# CAT-control-V1.net
KiCad netlist of a schematic drawn in EAGLE
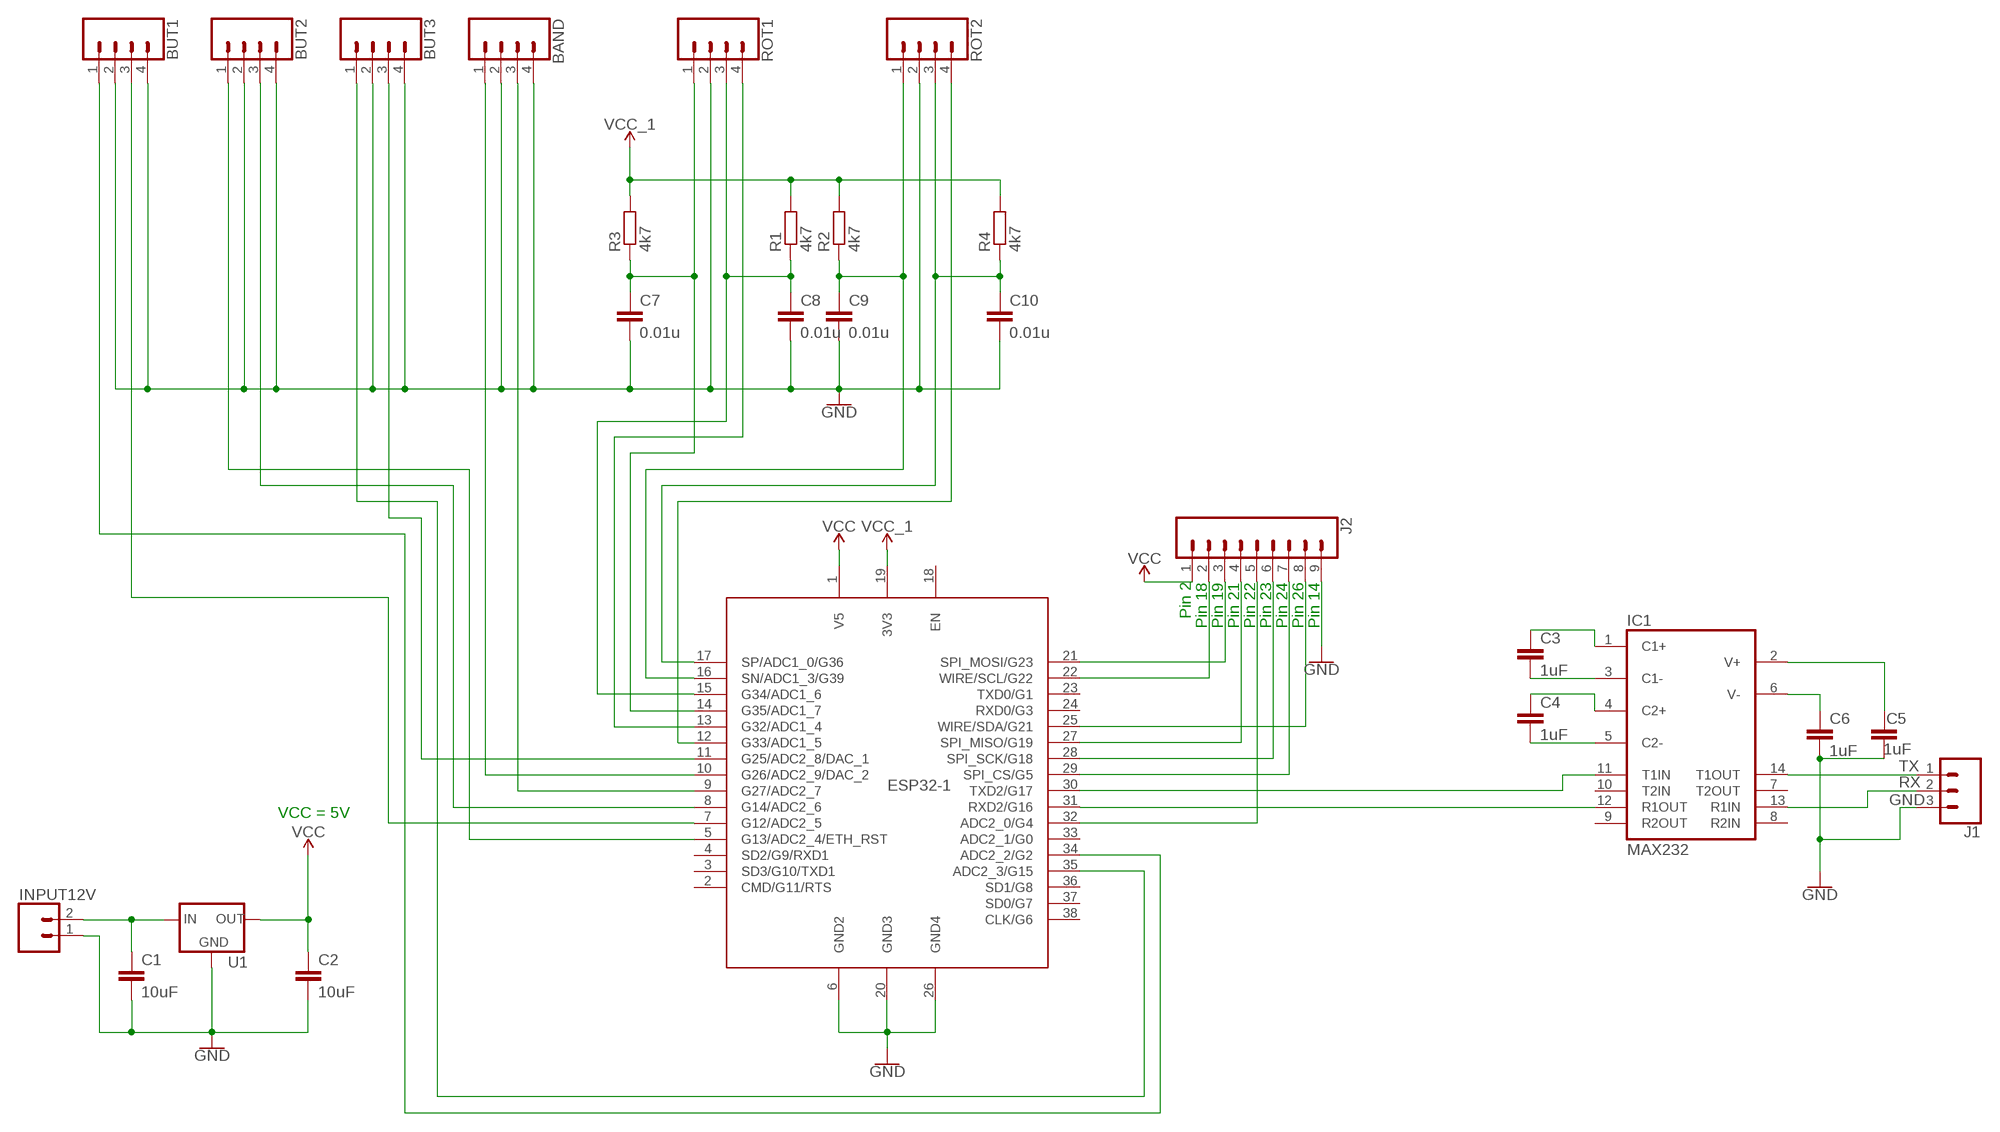
[diagram p0: schematic, sheet 1]

(export (version "E")
  (design (tool "Eeschema 10.0.6"))
  (components
    (comp (ref "BAND")
      (value "CONN_04POLAR")
      (footprint "eagle-import:MOLEX-1X4")
      (libsource (lib "eagle-import") (part "CONN_04POLAR"))
    )
    (comp (ref "BUT1")
      (value "CONN_04POLAR")
      (footprint "eagle-import:MOLEX-1X4")
      (libsource (lib "eagle-import") (part "CONN_04POLAR"))
    )
    (comp (ref "BUT2")
      (value "CONN_04POLAR")
      (footprint "eagle-import:MOLEX-1X4")
      (libsource (lib "eagle-import") (part "CONN_04POLAR"))
    )
    (comp (ref "BUT3")
      (value "CONN_04POLAR")
      (footprint "eagle-import:MOLEX-1X4")
      (libsource (lib "eagle-import") (part "CONN_04POLAR"))
    )
    (comp (ref "C1")
      (value "10uF")
      (footprint "eagle-import:C1206")
      (libsource (lib "eagle-import") (part "CAPACITORS-EUC1206"))
    )
    (comp (ref "C2")
      (value "10uF")
      (footprint "eagle-import:C1206")
      (libsource (lib "eagle-import") (part "CAPACITORS-EUC1206"))
    )
    (comp (ref "C3")
      (value "1uF")
      (footprint "eagle-import:C1206")
      (libsource (lib "eagle-import") (part "CAPACITORS-EUC1206"))
    )
    (comp (ref "C4")
      (value "1uF")
      (footprint "eagle-import:C1206")
      (libsource (lib "eagle-import") (part "CAPACITORS-EUC1206"))
    )
    (comp (ref "C5")
      (value "1uF")
      (footprint "eagle-import:C1206")
      (libsource (lib "eagle-import") (part "CAPACITORS-EUC1206"))
    )
    (comp (ref "C6")
      (value "1uF")
      (footprint "eagle-import:C1206")
      (libsource (lib "eagle-import") (part "CAPACITORS-EUC1206"))
    )
    (comp (ref "C7")
      (value "0.01u")
      (footprint "eagle-import:C025-024X044")
      (libsource (lib "eagle-import") (part "CAPACITORS-EU025-024X044"))
    )
    (comp (ref "C8")
      (value "0.01u")
      (footprint "eagle-import:C025-024X044")
      (libsource (lib "eagle-import") (part "CAPACITORS-EU025-024X044"))
    )
    (comp (ref "C9")
      (value "0.01u")
      (footprint "eagle-import:C025-024X044")
      (libsource (lib "eagle-import") (part "CAPACITORS-EU025-024X044"))
    )
    (comp (ref "C10")
      (value "0.01u")
      (footprint "eagle-import:C025-024X044")
      (libsource (lib "eagle-import") (part "CAPACITORS-EU025-024X044"))
    )
    (comp (ref "ESP32-1")
      (value "NODEMCU_ESP32_WROOM_32")
      (footprint "eagle-import:NODEMCU_ESP32_WROOM_32--38PINS")
      (libsource (lib "eagle-import") (part "NODEMCU_ESP32_WROOM_32"))
    )
    (comp (ref "IC1")
      (value "MAX232")
      (footprint "eagle-import:DIL16")
      (fields (field (name "MF") "MAXIM") (field (name "MPN") "MAX232ACPE+"))
      (libsource (lib "eagle-import") (part "MAX232"))
    )
    (comp (ref "INPUT12V")
      (value "CONN_025MM")
      (footprint "eagle-import:SCREWTERMINAL-5MM-2")
      (libsource (lib "eagle-import") (part "CONN_025MM"))
    )
    (comp (ref "J1")
      (value "CONN_03SCREW")
      (footprint "eagle-import:SCREWTERMINAL-3.5MM-3")
      (libsource (lib "eagle-import") (part "CONN_03SCREW"))
    )
    (comp (ref "J2")
      (value "CONN_09")
      (footprint "eagle-import:1X09")
      (libsource (lib "eagle-import") (part "CONN_09"))
    )
    (comp (ref "R1")
      (value "4k7")
      (footprint "eagle-import:R1206")
      (libsource (lib "eagle-import") (part "RESISTORS-EUR1206"))
    )
    (comp (ref "R2")
      (value "4k7")
      (footprint "eagle-import:R1206")
      (libsource (lib "eagle-import") (part "RESISTORS-EUR1206"))
    )
    (comp (ref "R3")
      (value "4k7")
      (footprint "eagle-import:R1206")
      (libsource (lib "eagle-import") (part "RESISTORS-EUR1206"))
    )
    (comp (ref "R4")
      (value "4k7")
      (footprint "eagle-import:R1206")
      (libsource (lib "eagle-import") (part "RESISTORS-EUR1206"))
    )
    (comp (ref "ROT1")
      (value "CONN_04POLAR")
      (footprint "eagle-import:MOLEX-1X4")
      (libsource (lib "eagle-import") (part "CONN_04POLAR"))
    )
    (comp (ref "ROT2")
      (value "CONN_04POLAR")
      (footprint "eagle-import:MOLEX-1X4")
      (libsource (lib "eagle-import") (part "CONN_04POLAR"))
    )
    (comp (ref "U1")
      (value "V_REG_78XXSINK")
      (footprint "eagle-import:TO220-IGO")
      (libsource (lib "eagle-import") (part "V_REG_78XXSINK"))
    )
  )
  (nets
    (net (code "1") (name "/CMD{slash}G11{slash}RTS") (class "Default")
      (node (ref "ESP32-1") (pin "2") (pinfunction "CMD/G11/RTS_2") (pintype "power_in"))
    )
    (net (code "2") (name "/RX") (class "Default")
      (node (ref "IC1") (pin "13") (pinfunction "R1IN_13") (pintype "input"))
      (node (ref "J1") (pin "2") (pinfunction "2_2") (pintype "passive"))
    )
    (net (code "3") (name "/TX") (class "Default")
      (node (ref "IC1") (pin "14") (pinfunction "T1OUT_14") (pintype "output"))
      (node (ref "J1") (pin "1") (pinfunction "1_1") (pintype "passive"))
    )
    (net (code "4") (name "GND") (class "Default")
      (node (ref "BAND") (pin "2") (pinfunction "2_2") (pintype "passive"))
      (node (ref "BAND") (pin "4") (pinfunction "4_4") (pintype "passive"))
      (node (ref "BUT1") (pin "2") (pinfunction "2_2") (pintype "passive"))
      (node (ref "BUT1") (pin "4") (pinfunction "4_4") (pintype "passive"))
      (node (ref "BUT2") (pin "2") (pinfunction "2_2") (pintype "passive"))
      (node (ref "BUT2") (pin "4") (pinfunction "4_4") (pintype "passive"))
      (node (ref "BUT3") (pin "2") (pinfunction "2_2") (pintype "passive"))
      (node (ref "BUT3") (pin "4") (pinfunction "4_4") (pintype "passive"))
      (node (ref "C1") (pin "2") (pinfunction "2_2") (pintype "passive"))
      (node (ref "C10") (pin "2") (pinfunction "2_2") (pintype "passive"))
      (node (ref "C2") (pin "2") (pinfunction "2_2") (pintype "passive"))
      (node (ref "C5") (pin "1") (pinfunction "1_1") (pintype "passive"))
      (node (ref "C6") (pin "2") (pinfunction "2_2") (pintype "passive"))
      (node (ref "C7") (pin "2") (pinfunction "2_2") (pintype "passive"))
      (node (ref "C8") (pin "2") (pinfunction "2_2") (pintype "passive"))
      (node (ref "C9") (pin "2") (pinfunction "2_2") (pintype "passive"))
      (node (ref "ESP32-1") (pin "20") (pinfunction "GND3_20") (pintype "power_in"))
      (node (ref "ESP32-1") (pin "26") (pinfunction "GND4_26") (pintype "power_in"))
      (node (ref "ESP32-1") (pin "6") (pinfunction "GND2_6") (pintype "power_in"))
      (node (ref "INPUT12V") (pin "1") (pinfunction "1_1") (pintype "passive"))
      (node (ref "J1") (pin "3") (pinfunction "3_3") (pintype "passive"))
      (node (ref "J2") (pin "9") (pinfunction "9_9") (pintype "passive"))
      (node (ref "ROT1") (pin "2") (pinfunction "2_2") (pintype "passive"))
      (node (ref "ROT2") (pin "2") (pinfunction "2_2") (pintype "passive"))
      (node (ref "U1") (pin "GND") (pinfunction "GND_GND") (pintype "input"))
    )
    (net (code "5") (name "Net-(C1-Pad1)") (class "Default")
      (node (ref "C1") (pin "1") (pinfunction "1_1") (pintype "passive"))
      (node (ref "INPUT12V") (pin "2") (pinfunction "2_2") (pintype "passive"))
      (node (ref "U1") (pin "IN") (pinfunction "IN_IN") (pintype "input"))
    )
    (net (code "6") (name "Net-(ESP32-1-ADC2_0{slash}G4)") (class "Default")
      (node (ref "ESP32-1") (pin "32") (pinfunction "ADC2_0/G4_32") (pintype "bidirectional"))
      (node (ref "J2") (pin "5") (pinfunction "5_5") (pintype "passive"))
    )
    (net (code "7") (name "Net-(ESP32-1-ADC2_2{slash}G2)") (class "Default")
      (node (ref "BUT1") (pin "1") (pinfunction "1_1") (pintype "passive"))
      (node (ref "ESP32-1") (pin "34") (pinfunction "ADC2_2/G2_34") (pintype "bidirectional"))
    )
    (net (code "8") (name "Net-(ESP32-1-ADC2_3{slash}G15)") (class "Default")
      (node (ref "BUT3") (pin "1") (pinfunction "1_1") (pintype "passive"))
      (node (ref "ESP32-1") (pin "35") (pinfunction "ADC2_3/G15_35") (pintype "bidirectional"))
    )
    (net (code "9") (name "Net-(ESP32-1-G12{slash}ADC2_5)") (class "Default")
      (node (ref "BUT1") (pin "3") (pinfunction "3_3") (pintype "passive"))
      (node (ref "ESP32-1") (pin "7") (pinfunction "G12/ADC2_5_7") (pintype "bidirectional"))
    )
    (net (code "10") (name "Net-(ESP32-1-G13{slash}ADC2_4{slash}ETH_RST)") (class "Default")
      (node (ref "BUT2") (pin "1") (pinfunction "1_1") (pintype "passive"))
      (node (ref "ESP32-1") (pin "5") (pinfunction "G13/ADC2_4/ETH_RST_5") (pintype "bidirectional"))
    )
    (net (code "11") (name "Net-(ESP32-1-G14{slash}ADC2_6)") (class "Default")
      (node (ref "BUT2") (pin "3") (pinfunction "3_3") (pintype "passive"))
      (node (ref "ESP32-1") (pin "8") (pinfunction "G14/ADC2_6_8") (pintype "bidirectional"))
    )
    (net (code "12") (name "Net-(ESP32-1-G25{slash}ADC2_8{slash}DAC_1)") (class "Default")
      (node (ref "BUT3") (pin "3") (pinfunction "3_3") (pintype "passive"))
      (node (ref "ESP32-1") (pin "11") (pinfunction "G25/ADC2_8/DAC_1_11") (pintype "bidirectional"))
    )
    (net (code "13") (name "Net-(ESP32-1-G26{slash}ADC2_9{slash}DAC_2)") (class "Default")
      (node (ref "BAND") (pin "1") (pinfunction "1_1") (pintype "passive"))
      (node (ref "ESP32-1") (pin "10") (pinfunction "G26/ADC2_9/DAC_2_10") (pintype "bidirectional"))
    )
    (net (code "14") (name "Net-(ESP32-1-G27{slash}ADC2_7)") (class "Default")
      (node (ref "BAND") (pin "3") (pinfunction "3_3") (pintype "passive"))
      (node (ref "ESP32-1") (pin "9") (pinfunction "G27/ADC2_7_9") (pintype "bidirectional"))
    )
    (net (code "15") (name "Net-(ESP32-1-G32{slash}ADC1_4)") (class "Default")
      (node (ref "ESP32-1") (pin "13") (pinfunction "G32/ADC1_4_13") (pintype "bidirectional"))
      (node (ref "ROT1") (pin "4") (pinfunction "4_4") (pintype "passive"))
    )
    (net (code "16") (name "Net-(ESP32-1-G33{slash}ADC1_5)") (class "Default")
      (node (ref "ESP32-1") (pin "12") (pinfunction "G33/ADC1_5_12") (pintype "bidirectional"))
      (node (ref "ROT2") (pin "4") (pinfunction "4_4") (pintype "passive"))
    )
    (net (code "17") (name "Net-(ESP32-1-G34{slash}ADC1_6)") (class "Default")
      (node (ref "C8") (pin "1") (pinfunction "1_1") (pintype "passive"))
      (node (ref "ESP32-1") (pin "15") (pinfunction "G34/ADC1_6_15") (pintype "bidirectional"))
      (node (ref "R1") (pin "1") (pinfunction "1_1") (pintype "passive"))
      (node (ref "ROT1") (pin "3") (pinfunction "3_3") (pintype "passive"))
    )
    (net (code "18") (name "Net-(ESP32-1-G35{slash}ADC1_7)") (class "Default")
      (node (ref "C7") (pin "1") (pinfunction "1_1") (pintype "passive"))
      (node (ref "ESP32-1") (pin "14") (pinfunction "G35/ADC1_7_14") (pintype "bidirectional"))
      (node (ref "R3") (pin "1") (pinfunction "1_1") (pintype "passive"))
      (node (ref "ROT1") (pin "1") (pinfunction "1_1") (pintype "passive"))
    )
    (net (code "19") (name "Net-(ESP32-1-RXD2{slash}G16)") (class "Default")
      (node (ref "ESP32-1") (pin "31") (pinfunction "RXD2/G16_31") (pintype "bidirectional"))
      (node (ref "IC1") (pin "12") (pinfunction "R1OUT_12") (pintype "output"))
    )
    (net (code "20") (name "Net-(ESP32-1-SN{slash}ADC1_3{slash}G39)") (class "Default")
      (node (ref "C9") (pin "1") (pinfunction "1_1") (pintype "passive"))
      (node (ref "ESP32-1") (pin "16") (pinfunction "SN/ADC1_3/G39_16") (pintype "bidirectional"))
      (node (ref "R2") (pin "1") (pinfunction "1_1") (pintype "passive"))
      (node (ref "ROT2") (pin "1") (pinfunction "1_1") (pintype "passive"))
    )
    (net (code "21") (name "Net-(ESP32-1-SPI_CS{slash}G5)") (class "Default")
      (node (ref "ESP32-1") (pin "29") (pinfunction "SPI_CS/G5_29") (pintype "bidirectional"))
      (node (ref "J2") (pin "7") (pinfunction "7_7") (pintype "passive"))
    )
    (net (code "22") (name "Net-(ESP32-1-SPI_MISO{slash}G19)") (class "Default")
      (node (ref "ESP32-1") (pin "27") (pinfunction "SPI_MISO/G19_27") (pintype "bidirectional"))
      (node (ref "J2") (pin "4") (pinfunction "4_4") (pintype "passive"))
    )
    (net (code "23") (name "Net-(ESP32-1-SPI_MOSI{slash}G23)") (class "Default")
      (node (ref "ESP32-1") (pin "21") (pinfunction "SPI_MOSI/G23_21") (pintype "bidirectional"))
      (node (ref "J2") (pin "3") (pinfunction "3_3") (pintype "passive"))
    )
    (net (code "24") (name "Net-(ESP32-1-SPI_SCK{slash}G18)") (class "Default")
      (node (ref "ESP32-1") (pin "28") (pinfunction "SPI_SCK/G18_28") (pintype "bidirectional"))
      (node (ref "J2") (pin "6") (pinfunction "6_6") (pintype "passive"))
    )
    (net (code "25") (name "Net-(ESP32-1-SP{slash}ADC1_0{slash}G36)") (class "Default")
      (node (ref "C10") (pin "1") (pinfunction "1_1") (pintype "passive"))
      (node (ref "ESP32-1") (pin "17") (pinfunction "SP/ADC1_0/G36_17") (pintype "bidirectional"))
      (node (ref "R4") (pin "1") (pinfunction "1_1") (pintype "passive"))
      (node (ref "ROT2") (pin "3") (pinfunction "3_3") (pintype "passive"))
    )
    (net (code "26") (name "Net-(ESP32-1-TXD2{slash}G17)") (class "Default")
      (node (ref "ESP32-1") (pin "30") (pinfunction "TXD2/G17_30") (pintype "bidirectional"))
      (node (ref "IC1") (pin "11") (pinfunction "T1IN_11") (pintype "input"))
    )
    (net (code "27") (name "Net-(ESP32-1-WIRE{slash}SCL{slash}G22)") (class "Default")
      (node (ref "ESP32-1") (pin "22") (pinfunction "WIRE/SCL/G22_22") (pintype "bidirectional"))
      (node (ref "J2") (pin "2") (pinfunction "2_2") (pintype "passive"))
    )
    (net (code "28") (name "Net-(ESP32-1-WIRE{slash}SDA{slash}G21)") (class "Default")
      (node (ref "ESP32-1") (pin "25") (pinfunction "WIRE/SDA/G21_25") (pintype "bidirectional"))
      (node (ref "J2") (pin "8") (pinfunction "8_8") (pintype "passive"))
    )
    (net (code "29") (name "Net-(IC1A-C1+)") (class "Default")
      (node (ref "C3") (pin "1") (pinfunction "1_1") (pintype "passive"))
      (node (ref "IC1") (pin "1") (pinfunction "C1+_1") (pintype "bidirectional"))
    )
    (net (code "30") (name "Net-(IC1A-C1-)") (class "Default")
      (node (ref "C3") (pin "2") (pinfunction "2_2") (pintype "passive"))
      (node (ref "IC1") (pin "3") (pinfunction "C1-_3") (pintype "bidirectional"))
    )
    (net (code "31") (name "Net-(IC1A-C2+)") (class "Default")
      (node (ref "C4") (pin "1") (pinfunction "1_1") (pintype "passive"))
      (node (ref "IC1") (pin "4") (pinfunction "C2+_4") (pintype "bidirectional"))
    )
    (net (code "32") (name "Net-(IC1A-C2-)") (class "Default")
      (node (ref "C4") (pin "2") (pinfunction "2_2") (pintype "passive"))
      (node (ref "IC1") (pin "5") (pinfunction "C2-_5") (pintype "bidirectional"))
    )
    (net (code "33") (name "Net-(IC1A-V+)") (class "Default")
      (node (ref "C5") (pin "2") (pinfunction "2_2") (pintype "passive"))
      (node (ref "IC1") (pin "2") (pinfunction "V+_2") (pintype "bidirectional"))
    )
    (net (code "34") (name "Net-(IC1A-V-)") (class "Default")
      (node (ref "C6") (pin "1") (pinfunction "1_1") (pintype "passive"))
      (node (ref "IC1") (pin "6") (pinfunction "V-_6") (pintype "bidirectional"))
    )
    (net (code "35") (name "VCC") (class "Default")
      (node (ref "C2") (pin "1") (pinfunction "1_1") (pintype "passive"))
      (node (ref "ESP32-1") (pin "1") (pinfunction "V5_1") (pintype "power_in"))
      (node (ref "J2") (pin "1") (pinfunction "1_1") (pintype "passive"))
      (node (ref "U1") (pin "OUT") (pinfunction "OUT_OUT") (pintype "passive"))
    )
    (net (code "36") (name "VCC_1") (class "Default")
      (node (ref "ESP32-1") (pin "19") (pinfunction "3V3_19") (pintype "power_in"))
      (node (ref "R1") (pin "2") (pinfunction "2_2") (pintype "passive"))
      (node (ref "R2") (pin "2") (pinfunction "2_2") (pintype "passive"))
      (node (ref "R3") (pin "2") (pinfunction "2_2") (pintype "passive"))
      (node (ref "R4") (pin "2") (pinfunction "2_2") (pintype "passive"))
    )
    (net (code "37") (name "unconnected-(ESP32-1-ADC2_1{slash}G0-Pad33)") (class "Default")
      (node (ref "ESP32-1") (pin "33") (pinfunction "ADC2_1/G0_33") (pintype "bidirectional"))
    )
    (net (code "38") (name "unconnected-(ESP32-1-CLK{slash}G6-Pad38)") (class "Default")
      (node (ref "ESP32-1") (pin "38") (pinfunction "CLK/G6_38") (pintype "bidirectional"))
    )
    (net (code "39") (name "unconnected-(ESP32-1-EN-Pad18)") (class "Default")
      (node (ref "ESP32-1") (pin "18") (pinfunction "EN_18") (pintype "bidirectional"))
    )
    (net (code "40") (name "unconnected-(ESP32-1-RXD0{slash}G3-Pad24)") (class "Default")
      (node (ref "ESP32-1") (pin "24") (pinfunction "RXD0/G3_24") (pintype "bidirectional"))
    )
    (net (code "41") (name "unconnected-(ESP32-1-SD0{slash}G7-Pad37)") (class "Default")
      (node (ref "ESP32-1") (pin "37") (pinfunction "SD0/G7_37") (pintype "bidirectional"))
    )
    (net (code "42") (name "unconnected-(ESP32-1-SD1{slash}G8-Pad36)") (class "Default")
      (node (ref "ESP32-1") (pin "36") (pinfunction "SD1/G8_36") (pintype "bidirectional"))
    )
    (net (code "43") (name "unconnected-(ESP32-1-SD2{slash}G9{slash}RXD1-Pad4)") (class "Default")
      (node (ref "ESP32-1") (pin "4") (pinfunction "SD2/G9/RXD1_4") (pintype "bidirectional"))
    )
    (net (code "44") (name "unconnected-(ESP32-1-SD3{slash}G10{slash}TXD1-Pad3)") (class "Default")
      (node (ref "ESP32-1") (pin "3") (pinfunction "SD3/G10/TXD1_3") (pintype "bidirectional"))
    )
    (net (code "45") (name "unconnected-(ESP32-1-TXD0{slash}G1-Pad23)") (class "Default")
      (node (ref "ESP32-1") (pin "23") (pinfunction "TXD0/G1_23") (pintype "bidirectional"))
    )
    (net (code "46") (name "unconnected-(IC1A-R2IN-Pad8)") (class "Default")
      (node (ref "IC1") (pin "8") (pinfunction "R2IN_8") (pintype "input"))
    )
    (net (code "47") (name "unconnected-(IC1A-R2OUT-Pad9)") (class "Default")
      (node (ref "IC1") (pin "9") (pinfunction "R2OUT_9") (pintype "output"))
    )
    (net (code "48") (name "unconnected-(IC1A-T2IN-Pad10)") (class "Default")
      (node (ref "IC1") (pin "10") (pinfunction "T2IN_10") (pintype "input"))
    )
    (net (code "49") (name "unconnected-(IC1A-T2OUT-Pad7)") (class "Default")
      (node (ref "IC1") (pin "7") (pinfunction "T2OUT_7") (pintype "output"))
    )
  )
)
